# Sheet2.net
KiCad netlist of a schematic drawn in Altium Designer
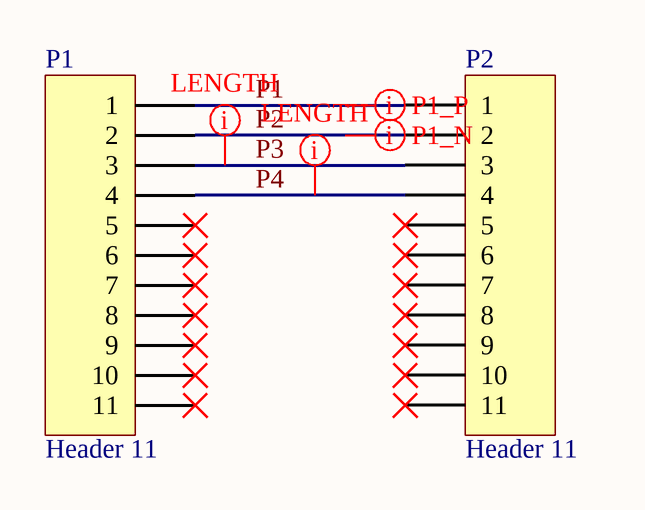
[diagram p0: Sheet2.SchDoc]

(export (version "E")
  (design (tool "Eeschema 10.0.6"))
  (components
    (comp (ref "P1")
      (value "Header 11")
      (footprint "HDR1X11")
      (description "Header, 11-Pin")
      (fields (field (name "PUBLISHER") "Altium Limited"))
      (libsource (lib "") (part "Header 11_1"))
    )
    (comp (ref "P2")
      (value "Header 11")
      (footprint "HDR1X11")
      (description "Header, 11-Pin")
      (fields (field (name "PUBLISHER") "Altium Limited"))
      (libsource (lib "Miscellaneous Connectors") (part "Header 11"))
    )
  )
  (nets
    (net (code "1") (name "/P1") (class "Default")
      (node (ref "P1") (pin "1") (pinfunction "1_1") (pintype "passive"))
      (node (ref "P2") (pin "1") (pinfunction "1_1") (pintype "passive"))
    )
    (net (code "2") (name "/P2") (class "Default")
      (node (ref "P1") (pin "2") (pinfunction "2_2") (pintype "passive"))
      (node (ref "P2") (pin "2") (pinfunction "2_2") (pintype "passive"))
    )
    (net (code "3") (name "/P3") (class "Default")
      (node (ref "P1") (pin "3") (pinfunction "3_3") (pintype "passive"))
      (node (ref "P2") (pin "3") (pinfunction "3_3") (pintype "passive"))
    )
    (net (code "4") (name "/P4") (class "Default")
      (node (ref "P1") (pin "4") (pinfunction "4_4") (pintype "passive"))
      (node (ref "P2") (pin "4") (pinfunction "4_4") (pintype "passive"))
    )
    (net (code "5") (name "unconnected-(P1-Pad5)") (class "Default")
      (node (ref "P1") (pin "5") (pinfunction "5_5") (pintype "passive+no_connect"))
    )
    (net (code "6") (name "unconnected-(P1-Pad6)") (class "Default")
      (node (ref "P1") (pin "6") (pinfunction "6_6") (pintype "passive+no_connect"))
    )
    (net (code "7") (name "unconnected-(P1-Pad7)") (class "Default")
      (node (ref "P1") (pin "7") (pinfunction "7_7") (pintype "passive+no_connect"))
    )
    (net (code "8") (name "unconnected-(P1-Pad8)") (class "Default")
      (node (ref "P1") (pin "8") (pinfunction "8_8") (pintype "passive+no_connect"))
    )
    (net (code "9") (name "unconnected-(P1-Pad9)") (class "Default")
      (node (ref "P1") (pin "9") (pinfunction "9_9") (pintype "passive+no_connect"))
    )
    (net (code "10") (name "unconnected-(P1-Pad10)") (class "Default")
      (node (ref "P1") (pin "10") (pinfunction "10_10") (pintype "passive+no_connect"))
    )
    (net (code "11") (name "unconnected-(P1-Pad11)") (class "Default")
      (node (ref "P1") (pin "11") (pinfunction "11_11") (pintype "passive+no_connect"))
    )
    (net (code "12") (name "unconnected-(P2-Pad5)") (class "Default")
      (node (ref "P2") (pin "5") (pinfunction "5_5") (pintype "passive+no_connect"))
    )
    (net (code "13") (name "unconnected-(P2-Pad6)") (class "Default")
      (node (ref "P2") (pin "6") (pinfunction "6_6") (pintype "passive+no_connect"))
    )
    (net (code "14") (name "unconnected-(P2-Pad7)") (class "Default")
      (node (ref "P2") (pin "7") (pinfunction "7_7") (pintype "passive+no_connect"))
    )
    (net (code "15") (name "unconnected-(P2-Pad8)") (class "Default")
      (node (ref "P2") (pin "8") (pinfunction "8_8") (pintype "passive+no_connect"))
    )
    (net (code "16") (name "unconnected-(P2-Pad9)") (class "Default")
      (node (ref "P2") (pin "9") (pinfunction "9_9") (pintype "passive+no_connect"))
    )
    (net (code "17") (name "unconnected-(P2-Pad10)") (class "Default")
      (node (ref "P2") (pin "10") (pinfunction "10_10") (pintype "passive+no_connect"))
    )
    (net (code "18") (name "unconnected-(P2-Pad11)") (class "Default")
      (node (ref "P2") (pin "11") (pinfunction "11_11") (pintype "passive+no_connect"))
    )
  )
)
